# Power_Input.net
KiCad netlist of a schematic drawn in Altium Designer
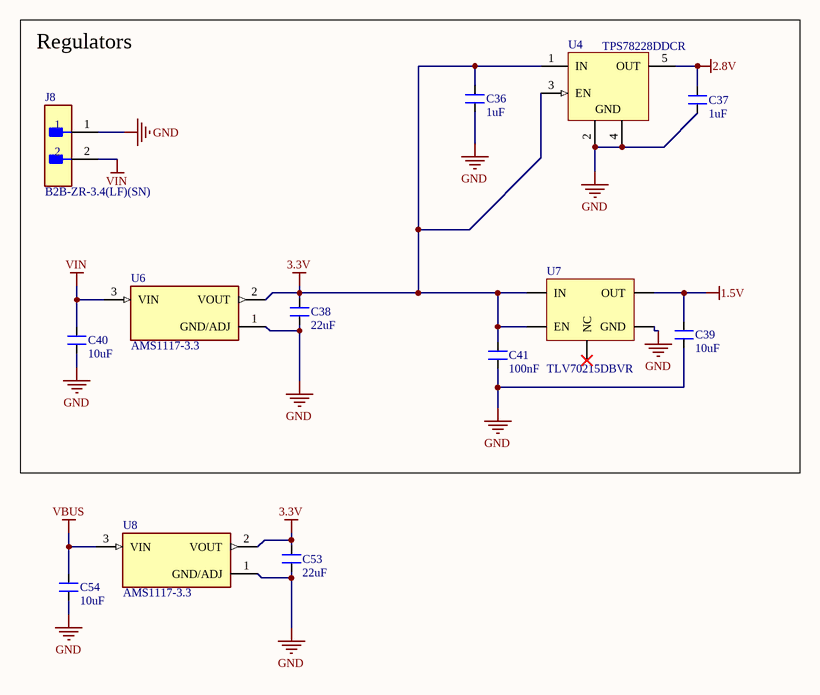
[diagram p0: Power Input.SchDoc]

(export (version "E")
  (design (tool "Eeschema 10.0.6"))
  (components
    (comp (ref "C36")
      (value "1uF")
      (footprint "CAP_0805")
      (description "10000pF ±10% 50V Ceramic Capacitor X7R 0805 (2012 Metric)")
      (fields
        (field (name "MANUFACTURER") "Samsung")
        (field (name "MANUFACTURER PART NUMBER") "C0805C103K5RECAUTO")
      )
      (libsource (lib "ESTEEMPCBLIB") (part "CAP_10nF-50V-10%-0805"))
    )
    (comp (ref "C37")
      (value "1uF")
      (footprint "CAP_0805")
      (description "10000pF ±10% 50V Ceramic Capacitor X7R 0805 (2012 Metric)")
      (fields
        (field (name "MANUFACTURER") "Samsung")
        (field (name "MANUFACTURER PART NUMBER") "C0805C103K5RECAUTO")
      )
      (libsource (lib "ESTEEMPCBLIB") (part "CAP_10nF-50V-10%-0805"))
    )
    (comp (ref "C38")
      (value "22uF")
      (footprint "CAP_0805")
      (description "22µF ±20% 25V Ceramic Capacitor X5R 0805 (2012 Metric)")
      (fields
        (field (name "MANUFACTURER") "Murata")
        (field (name "MANUFACTURER PART NUMBER") "GRM21BR61E226ME44L")
      )
      (libsource (lib "ESTEEMPCBLIB") (part "CAP_22uF-25V-20%-0805"))
    )
    (comp (ref "C39")
      (value "10uF")
      (footprint "CAP_0805")
      (description "10000pF ±10% 50V Ceramic Capacitor X7R 0805 (2012 Metric)")
      (fields
        (field (name "MANUFACTURER") "Samsung")
        (field (name "MANUFACTURER PART NUMBER") "C0805C103K5RECAUTO")
      )
      (libsource (lib "ESTEEMPCBLIB") (part "CAP_10nF-50V-10%-0805"))
    )
    (comp (ref "C40")
      (value "10uF")
      (footprint "CAP_0805")
      (description "10000pF ±10% 50V Ceramic Capacitor X7R 0805 (2012 Metric)")
      (fields
        (field (name "MANUFACTURER") "Samsung")
        (field (name "MANUFACTURER PART NUMBER") "C0805C103K5RECAUTO")
      )
      (libsource (lib "ESTEEMPCBLIB") (part "CAP_10nF-50V-10%-0805"))
    )
    (comp (ref "C41")
      (value "100nF")
      (footprint "CAP_0805")
      (description "10000pF ±10% 50V Ceramic Capacitor X7R 0805 (2012 Metric)")
      (fields
        (field (name "MANUFACTURER") "Samsung")
        (field (name "MANUFACTURER PART NUMBER") "C0805C103K5RECAUTO")
      )
      (libsource (lib "ESTEEMPCBLIB") (part "CAP_10nF-50V-10%-0805"))
    )
    (comp (ref "C53")
      (value "22uF")
      (footprint "CAP_0805")
      (description "22µF ±20% 25V Ceramic Capacitor X5R 0805 (2012 Metric)")
      (fields
        (field (name "MANUFACTURER") "Murata")
        (field (name "MANUFACTURER PART NUMBER") "GRM21BR61E226ME44L")
      )
      (libsource (lib "ESTEEMPCBLIB") (part "CAP_22uF-25V-20%-0805"))
    )
    (comp (ref "C54")
      (value "10uF")
      (footprint "CAP_0805")
      (description "10000pF ±10% 50V Ceramic Capacitor X7R 0805 (2012 Metric)")
      (fields
        (field (name "MANUFACTURER") "Samsung")
        (field (name "MANUFACTURER PART NUMBER") "C0805C103K5RECAUTO")
      )
      (libsource (lib "ESTEEMPCBLIB") (part "CAP_10nF-50V-10%-0805"))
    )
    (comp (ref "J8")
      (value "B2B-ZR-3.4(LF)(SN)")
      (footprint "FP-B2B-ZR-3_4_LF_SN-MFG")
      (description "CONN HEADER VERT 2POS 1.5MM")
      (libsource (lib "Altium Content Vault") (part "3bc925449376181038e59eaffc5286c"))
    )
    (comp (ref "U4")
      (value "TPS78228DDCR")
      (footprint "DDC0005A_L")
      (fields (field (name "MANUFACTURER") "Texas Instruments"))
      (libsource (lib "Altium Content Vault") (part "TI-TPS78XXX-DDC5"))
    )
    (comp (ref "U6")
      (value "AMS1117-3.3")
      (footprint "SOT229P700X180-4N")
      (description "Sot223/Pkg 1-Amp 3.3-Volt Low Drop Out Voltage Regulatator")
      (fields (field (name "MF") "Advanced Monolithic Systems"))
      (libsource (lib "AMS1117-3.3 (1)") (part "AMS1117-3.3"))
    )
    (comp (ref "U7")
      (value "TLV70215DBVR")
      (footprint "TLV70215DBVR")
      (libsource (lib "VoltaRoket") (part "TLV70215DBVR"))
    )
    (comp (ref "U8")
      (value "AMS1117-3.3")
      (footprint "SOT229P700X180-4N")
      (description "Sot223/Pkg 1-Amp 3.3-Volt Low Drop Out Voltage Regulatator")
      (fields (field (name "MF") "Advanced Monolithic Systems"))
      (libsource (lib "AMS1117-3.3 (1)") (part "AMS1117-3.3"))
    )
  )
  (nets
    (net (code "1") (name "1.5V") (class "Default")
      (node (ref "C39") (pin "2") (pinfunction "2_2") (pintype "passive"))
      (node (ref "U7") (pin "5") (pinfunction "OUT_5") (pintype "passive"))
    )
    (net (code "2") (name "2.8V") (class "Default")
      (node (ref "C37") (pin "2") (pinfunction "2_2") (pintype "passive"))
      (node (ref "U4") (pin "5") (pinfunction "OUT_5") (pintype "power_in"))
    )
    (net (code "3") (name "3.3V") (class "Default")
      (node (ref "C36") (pin "2") (pinfunction "2_2") (pintype "passive"))
      (node (ref "C38") (pin "2") (pinfunction "2_2") (pintype "passive"))
      (node (ref "C41") (pin "2") (pinfunction "2_2") (pintype "passive"))
      (node (ref "C53") (pin "2") (pinfunction "2_2") (pintype "passive"))
      (node (ref "U4") (pin "1") (pinfunction "IN_1") (pintype "power_in"))
      (node (ref "U4") (pin "3") (pinfunction "EN_3") (pintype "input"))
      (node (ref "U6") (pin "2") (pinfunction "VOUT_2") (pintype "output"))
      (node (ref "U7") (pin "1") (pinfunction "IN_1") (pintype "passive"))
      (node (ref "U7") (pin "3") (pinfunction "EN_3") (pintype "passive"))
      (node (ref "U8") (pin "2") (pinfunction "VOUT_2") (pintype "output"))
    )
    (net (code "4") (name "GND") (class "Default")
      (node (ref "C36") (pin "1") (pinfunction "1_1") (pintype "passive"))
      (node (ref "C37") (pin "1") (pinfunction "1_1") (pintype "passive"))
      (node (ref "C38") (pin "1") (pinfunction "1_1") (pintype "passive"))
      (node (ref "C39") (pin "1") (pinfunction "1_1") (pintype "passive"))
      (node (ref "C40") (pin "1") (pinfunction "1_1") (pintype "passive"))
      (node (ref "C41") (pin "1") (pinfunction "1_1") (pintype "passive"))
      (node (ref "C53") (pin "1") (pinfunction "1_1") (pintype "passive"))
      (node (ref "C54") (pin "1") (pinfunction "1_1") (pintype "passive"))
      (node (ref "J8") (pin "1") (pinfunction "1_1") (pintype "passive"))
      (node (ref "U4") (pin "2") (pinfunction "GND_2") (pintype "power_in"))
      (node (ref "U4") (pin "4") (pinfunction "GND_4") (pintype "power_in"))
      (node (ref "U6") (pin "1") (pinfunction "GND/ADJ_1") (pintype "power_in"))
      (node (ref "U7") (pin "2") (pinfunction "GND_2") (pintype "passive"))
      (node (ref "U8") (pin "1") (pinfunction "GND/ADJ_1") (pintype "power_in"))
    )
    (net (code "5") (name "VBUS") (class "Default")
      (node (ref "C54") (pin "2") (pinfunction "2_2") (pintype "passive"))
      (node (ref "U8") (pin "3") (pinfunction "VIN_3") (pintype "input"))
    )
    (net (code "6") (name "VIN") (class "Default")
      (node (ref "C40") (pin "2") (pinfunction "2_2") (pintype "passive"))
      (node (ref "J8") (pin "2") (pinfunction "2_2") (pintype "passive"))
      (node (ref "U6") (pin "3") (pinfunction "VIN_3") (pintype "input"))
    )
    (net (code "7") (name "unconnected-(U7-NC-Pad4)") (class "Default")
      (node (ref "U7") (pin "4") (pinfunction "NC_4") (pintype "passive+no_connect"))
    )
  )
)
